# bike-computer.net
KiCad netlist of a schematic drawn in EAGLE
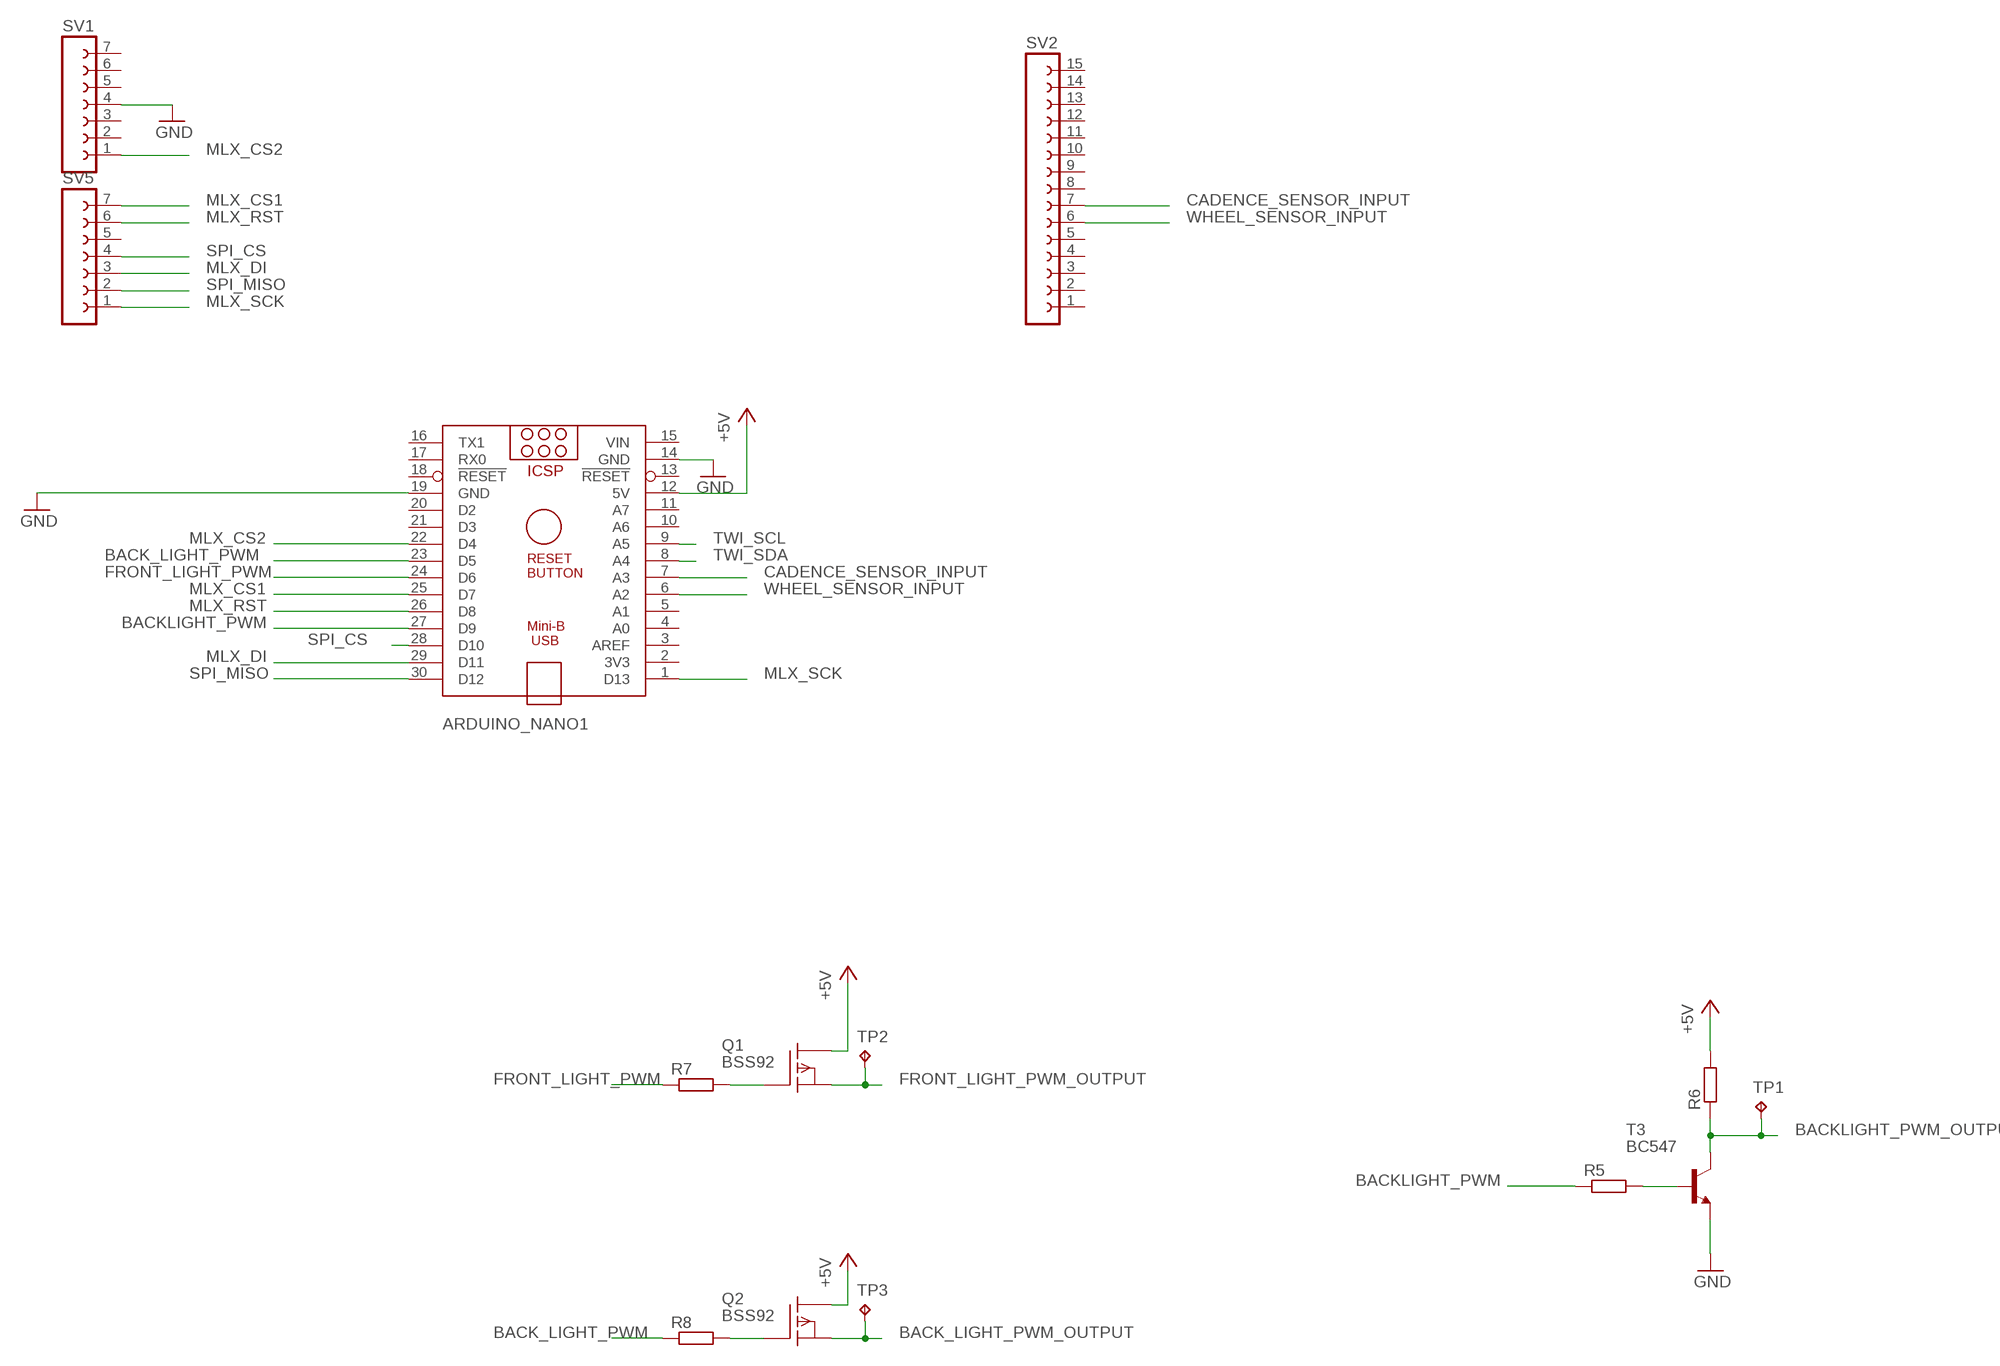
[diagram p0: schematic, sheet 1]

(export (version "E")
  (design (tool "Eeschema 10.0.6"))
  (components
    (comp (ref "ARDUINO_NANO1")
      (value "ARDUINO_NANO")
      (footprint "eagle-import:ARDUINO_NANO")
      (libsource (lib "eagle-import") (part "ARDUINO_NANO"))
    )
    (comp (ref "Q1")
      (value "BSS92")
      (footprint "eagle-import:TO92")
      (libsource (lib "eagle-import") (part "BSS92"))
    )
    (comp (ref "Q2")
      (value "BSS92")
      (footprint "eagle-import:TO92")
      (libsource (lib "eagle-import") (part "BSS92"))
    )
    (comp (ref "R5")
      (value "R-EU_0204/5")
      (footprint "eagle-import:0204_5")
      (libsource (lib "eagle-import") (part "R-EU_0204/5"))
    )
    (comp (ref "R6")
      (value "R-EU_0207/10")
      (footprint "eagle-import:0207_10")
      (libsource (lib "eagle-import") (part "R-EU_0207/10"))
    )
    (comp (ref "R7")
      (value "R-EU_0204/5")
      (footprint "eagle-import:0204_5")
      (libsource (lib "eagle-import") (part "R-EU_0204/5"))
    )
    (comp (ref "R8")
      (value "R-EU_0204/5")
      (footprint "eagle-import:0204_5")
      (libsource (lib "eagle-import") (part "R-EU_0204/5"))
    )
    (comp (ref "SV1")
      (value "FE07-1")
      (footprint "eagle-import:FE07")
      (libsource (lib "eagle-import") (part "FE07-1"))
    )
    (comp (ref "SV2")
      (value "FE15-1")
      (footprint "eagle-import:FE15")
      (libsource (lib "eagle-import") (part "FE15-1"))
    )
    (comp (ref "SV5")
      (value "FE07-1")
      (footprint "eagle-import:FE07")
      (libsource (lib "eagle-import") (part "FE07-1"))
    )
    (comp (ref "T3")
      (value "BC547")
      (footprint "eagle-import:TO92")
      (libsource (lib "eagle-import") (part "BC547"))
    )
    (comp (ref "TP1")
      (value "TPPAD1-13")
      (footprint "eagle-import:P1-13")
      (libsource (lib "eagle-import") (part "TPPAD1-13"))
    )
    (comp (ref "TP2")
      (value "TPPAD1-13")
      (footprint "eagle-import:P1-13")
      (libsource (lib "eagle-import") (part "TPPAD1-13"))
    )
    (comp (ref "TP3")
      (value "TPPAD1-13")
      (footprint "eagle-import:P1-13")
      (libsource (lib "eagle-import") (part "TPPAD1-13"))
    )
  )
  (nets
    (net (code "1") (name "+5V") (class "Default")
      (node (ref "ARDUINO_NANO1") (pin "12") (pinfunction "5V_12") (pintype "power_in"))
      (node (ref "Q1") (pin "2") (pinfunction "D_2") (pintype "passive"))
      (node (ref "Q2") (pin "2") (pinfunction "D_2") (pintype "passive"))
      (node (ref "R6") (pin "2") (pinfunction "2_2") (pintype "passive"))
    )
    (net (code "2") (name "/BACKLIGHT_PWM") (class "Default")
      (node (ref "ARDUINO_NANO1") (pin "27") (pinfunction "D9_27") (pintype "bidirectional"))
      (node (ref "R5") (pin "1") (pinfunction "1_1") (pintype "passive"))
    )
    (net (code "3") (name "/BACKLIGHT_PWM_OUTPUT") (class "Default")
      (node (ref "R6") (pin "1") (pinfunction "1_1") (pintype "passive"))
      (node (ref "T3") (pin "3") (pinfunction "C_3") (pintype "passive"))
      (node (ref "TP1") (pin "TP") (pinfunction "TP_TP") (pintype "input"))
    )
    (net (code "4") (name "/BACK_LIGHT_PWM") (class "Default")
      (node (ref "ARDUINO_NANO1") (pin "23") (pinfunction "D5_23") (pintype "bidirectional"))
      (node (ref "R8") (pin "1") (pinfunction "1_1") (pintype "passive"))
    )
    (net (code "5") (name "/BACK_LIGHT_PWM_OUTPUT") (class "Default")
      (node (ref "Q2") (pin "3") (pinfunction "S_3") (pintype "passive"))
      (node (ref "TP3") (pin "TP") (pinfunction "TP_TP") (pintype "input"))
    )
    (net (code "6") (name "/CADENCE_SENSOR_INPUT") (class "Default")
      (node (ref "ARDUINO_NANO1") (pin "7") (pinfunction "A3_7") (pintype "bidirectional"))
      (node (ref "SV2") (pin "7") (pinfunction "7_7") (pintype "passive"))
    )
    (net (code "7") (name "/FRONT_LIGHT_PWM") (class "Default")
      (node (ref "ARDUINO_NANO1") (pin "24") (pinfunction "D6_24") (pintype "bidirectional"))
      (node (ref "R7") (pin "1") (pinfunction "1_1") (pintype "passive"))
    )
    (net (code "8") (name "/FRONT_LIGHT_PWM_OUTPUT") (class "Default")
      (node (ref "Q1") (pin "3") (pinfunction "S_3") (pintype "passive"))
      (node (ref "TP2") (pin "TP") (pinfunction "TP_TP") (pintype "input"))
    )
    (net (code "9") (name "/MLX_CS1") (class "Default")
      (node (ref "ARDUINO_NANO1") (pin "25") (pinfunction "D7_25") (pintype "bidirectional"))
      (node (ref "SV5") (pin "7") (pinfunction "7_7") (pintype "passive"))
    )
    (net (code "10") (name "/MLX_CS2") (class "Default")
      (node (ref "ARDUINO_NANO1") (pin "22") (pinfunction "D4_22") (pintype "bidirectional"))
      (node (ref "SV1") (pin "1") (pinfunction "1_1") (pintype "passive"))
    )
    (net (code "11") (name "/MLX_DI") (class "Default")
      (node (ref "ARDUINO_NANO1") (pin "29") (pinfunction "D11_29") (pintype "bidirectional"))
      (node (ref "SV5") (pin "3") (pinfunction "3_3") (pintype "passive"))
    )
    (net (code "12") (name "/MLX_RST") (class "Default")
      (node (ref "ARDUINO_NANO1") (pin "26") (pinfunction "D8_26") (pintype "bidirectional"))
      (node (ref "SV5") (pin "6") (pinfunction "6_6") (pintype "passive"))
    )
    (net (code "13") (name "/MLX_SCK") (class "Default")
      (node (ref "ARDUINO_NANO1") (pin "1") (pinfunction "D13_1") (pintype "bidirectional"))
      (node (ref "SV5") (pin "1") (pinfunction "1_1") (pintype "passive"))
    )
    (net (code "14") (name "/SPI_CS") (class "Default")
      (node (ref "ARDUINO_NANO1") (pin "28") (pinfunction "D10_28") (pintype "bidirectional"))
      (node (ref "SV5") (pin "4") (pinfunction "4_4") (pintype "passive"))
    )
    (net (code "15") (name "/SPI_MISO") (class "Default")
      (node (ref "ARDUINO_NANO1") (pin "30") (pinfunction "D12_30") (pintype "bidirectional"))
      (node (ref "SV5") (pin "2") (pinfunction "2_2") (pintype "passive"))
    )
    (net (code "16") (name "/TWI_SCL") (class "Default")
      (node (ref "ARDUINO_NANO1") (pin "9") (pinfunction "A5_9") (pintype "bidirectional"))
    )
    (net (code "17") (name "/TWI_SDA") (class "Default")
      (node (ref "ARDUINO_NANO1") (pin "8") (pinfunction "A4_8") (pintype "bidirectional"))
    )
    (net (code "18") (name "/VIN") (class "Default")
      (node (ref "ARDUINO_NANO1") (pin "15") (pinfunction "VIN_15") (pintype "power_in"))
    )
    (net (code "19") (name "/WHEEL_SENSOR_INPUT") (class "Default")
      (node (ref "ARDUINO_NANO1") (pin "6") (pinfunction "A2_6") (pintype "bidirectional"))
      (node (ref "SV2") (pin "6") (pinfunction "6_6") (pintype "passive"))
    )
    (net (code "20") (name "GND") (class "Default")
      (node (ref "ARDUINO_NANO1") (pin "14") (pinfunction "GND_14") (pintype "power_in"))
      (node (ref "ARDUINO_NANO1") (pin "19") (pinfunction "GND_19") (pintype "power_in"))
      (node (ref "SV1") (pin "4") (pinfunction "4_4") (pintype "passive"))
      (node (ref "T3") (pin "1") (pinfunction "E_1") (pintype "passive"))
    )
    (net (code "21") (name "Net-(Q1-G)") (class "Default")
      (node (ref "Q1") (pin "1") (pinfunction "G_1") (pintype "passive"))
      (node (ref "R7") (pin "2") (pinfunction "2_2") (pintype "passive"))
    )
    (net (code "22") (name "Net-(Q2-G)") (class "Default")
      (node (ref "Q2") (pin "1") (pinfunction "G_1") (pintype "passive"))
      (node (ref "R8") (pin "2") (pinfunction "2_2") (pintype "passive"))
    )
    (net (code "23") (name "Net-(T3-B)") (class "Default")
      (node (ref "R5") (pin "2") (pinfunction "2_2") (pintype "passive"))
      (node (ref "T3") (pin "2") (pinfunction "B_2") (pintype "passive"))
    )
    (net (code "24") (name "unconnected-(ARDUINO_NANO1-3V3-Pad2)") (class "Default")
      (node (ref "ARDUINO_NANO1") (pin "2") (pinfunction "3V3_2") (pintype "output"))
    )
    (net (code "25") (name "unconnected-(ARDUINO_NANO1-A0-Pad4)") (class "Default")
      (node (ref "ARDUINO_NANO1") (pin "4") (pinfunction "A0_4") (pintype "bidirectional"))
    )
    (net (code "26") (name "unconnected-(ARDUINO_NANO1-A1-Pad5)") (class "Default")
      (node (ref "ARDUINO_NANO1") (pin "5") (pinfunction "A1_5") (pintype "bidirectional"))
    )
    (net (code "27") (name "unconnected-(ARDUINO_NANO1-A6-Pad10)") (class "Default")
      (node (ref "ARDUINO_NANO1") (pin "10") (pinfunction "A6_10") (pintype "bidirectional"))
    )
    (net (code "28") (name "unconnected-(ARDUINO_NANO1-A7-Pad11)") (class "Default")
      (node (ref "ARDUINO_NANO1") (pin "11") (pinfunction "A7_11") (pintype "bidirectional"))
    )
    (net (code "29") (name "unconnected-(ARDUINO_NANO1-AREF-Pad3)") (class "Default")
      (node (ref "ARDUINO_NANO1") (pin "3") (pinfunction "AREF_3") (pintype "input"))
    )
    (net (code "30") (name "unconnected-(ARDUINO_NANO1-D2-Pad20)") (class "Default")
      (node (ref "ARDUINO_NANO1") (pin "20") (pinfunction "D2_20") (pintype "bidirectional"))
    )
    (net (code "31") (name "unconnected-(ARDUINO_NANO1-D3-Pad21)") (class "Default")
      (node (ref "ARDUINO_NANO1") (pin "21") (pinfunction "D3_21") (pintype "bidirectional"))
    )
    (net (code "32") (name "unconnected-(ARDUINO_NANO1-RX0-Pad17)") (class "Default")
      (node (ref "ARDUINO_NANO1") (pin "17") (pinfunction "RX0_17") (pintype "bidirectional"))
    )
    (net (code "33") (name "unconnected-(ARDUINO_NANO1-TX1-Pad16)") (class "Default")
      (node (ref "ARDUINO_NANO1") (pin "16") (pinfunction "TX1_16") (pintype "bidirectional"))
    )
    (net (code "34") (name "unconnected-(ARDUINO_NANO1-~{RESET}-Pad13)") (class "Default")
      (node (ref "ARDUINO_NANO1") (pin "13") (pinfunction "~{RESET}_13") (pintype "input"))
    )
    (net (code "35") (name "unconnected-(ARDUINO_NANO1-~{RESET}-Pad18)") (class "Default")
      (node (ref "ARDUINO_NANO1") (pin "18") (pinfunction "~{RESET}_18") (pintype "input"))
    )
    (net (code "36") (name "unconnected-(SV1-Pad2)") (class "Default")
      (node (ref "SV1") (pin "2") (pinfunction "2_2") (pintype "passive"))
    )
    (net (code "37") (name "unconnected-(SV1-Pad3)") (class "Default")
      (node (ref "SV1") (pin "3") (pinfunction "3_3") (pintype "passive"))
    )
    (net (code "38") (name "unconnected-(SV1-Pad5)") (class "Default")
      (node (ref "SV1") (pin "5") (pinfunction "5_5") (pintype "passive"))
    )
    (net (code "39") (name "unconnected-(SV1-Pad6)") (class "Default")
      (node (ref "SV1") (pin "6") (pinfunction "6_6") (pintype "passive"))
    )
    (net (code "40") (name "unconnected-(SV1-Pad7)") (class "Default")
      (node (ref "SV1") (pin "7") (pinfunction "7_7") (pintype "passive"))
    )
    (net (code "41") (name "unconnected-(SV2-Pad1)") (class "Default")
      (node (ref "SV2") (pin "1") (pinfunction "1_1") (pintype "passive"))
    )
    (net (code "42") (name "unconnected-(SV2-Pad2)") (class "Default")
      (node (ref "SV2") (pin "2") (pinfunction "2_2") (pintype "passive"))
    )
    (net (code "43") (name "unconnected-(SV2-Pad3)") (class "Default")
      (node (ref "SV2") (pin "3") (pinfunction "3_3") (pintype "passive"))
    )
    (net (code "44") (name "unconnected-(SV2-Pad4)") (class "Default")
      (node (ref "SV2") (pin "4") (pinfunction "4_4") (pintype "passive"))
    )
    (net (code "45") (name "unconnected-(SV2-Pad5)") (class "Default")
      (node (ref "SV2") (pin "5") (pinfunction "5_5") (pintype "passive"))
    )
    (net (code "46") (name "unconnected-(SV2-Pad8)") (class "Default")
      (node (ref "SV2") (pin "8") (pinfunction "8_8") (pintype "passive"))
    )
    (net (code "47") (name "unconnected-(SV2-Pad9)") (class "Default")
      (node (ref "SV2") (pin "9") (pinfunction "9_9") (pintype "passive"))
    )
    (net (code "48") (name "unconnected-(SV2-Pad10)") (class "Default")
      (node (ref "SV2") (pin "10") (pinfunction "10_10") (pintype "passive"))
    )
    (net (code "49") (name "unconnected-(SV2-Pad11)") (class "Default")
      (node (ref "SV2") (pin "11") (pinfunction "11_11") (pintype "passive"))
    )
    (net (code "50") (name "unconnected-(SV2-Pad12)") (class "Default")
      (node (ref "SV2") (pin "12") (pinfunction "12_12") (pintype "passive"))
    )
    (net (code "51") (name "unconnected-(SV2-Pad13)") (class "Default")
      (node (ref "SV2") (pin "13") (pinfunction "13_13") (pintype "passive"))
    )
    (net (code "52") (name "unconnected-(SV2-Pad14)") (class "Default")
      (node (ref "SV2") (pin "14") (pinfunction "14_14") (pintype "passive"))
    )
    (net (code "53") (name "unconnected-(SV2-Pad15)") (class "Default")
      (node (ref "SV2") (pin "15") (pinfunction "15_15") (pintype "passive"))
    )
    (net (code "54") (name "unconnected-(SV5-Pad5)") (class "Default")
      (node (ref "SV5") (pin "5") (pinfunction "5_5") (pintype "passive"))
    )
  )
)
